# PowerBoard.net
KiCad netlist of a schematic drawn in EAGLE
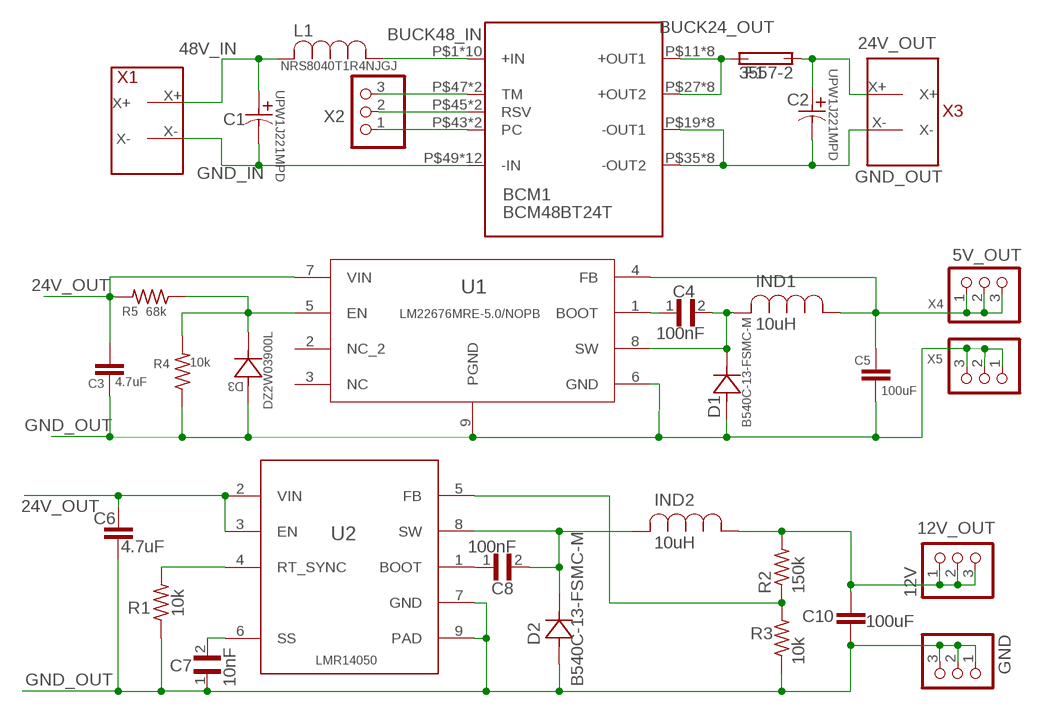
[diagram p0: schematic, sheet 1]

(export (version "E")
  (design (tool "Eeschema 10.0.6"))
  (components
    (comp (ref "12V")
      (value "9-146281-0")
      (footprint "eagle-import:TE_9-146281-0")
      (fields (field (name "MF") "TE Connectivity"))
      (libsource (lib "eagle-import") (part "9-146281-0"))
    )
    (comp (ref "BCM1")
      (value "BCM48BT24T")
      (footprint "eagle-import:BCM48BT24T")
      (libsource (lib "eagle-import") (part "BCM48BT24T"))
    )
    (comp (ref "C1")
      (value "UPW1J221MPD")
      (footprint "eagle-import:PCAP_10X20-THRU-ELECT")
      (libsource (lib "eagle-import") (part "UPW1J221MPD"))
    )
    (comp (ref "C2")
      (value "UPW1J221MPD")
      (footprint "eagle-import:PCAP_10X20-THRU-ELECT")
      (libsource (lib "eagle-import") (part "UPW1J221MPD"))
    )
    (comp (ref "C3")
      (value "4.7uF")
      (footprint "eagle-import:0603")
      (libsource (lib "eagle-import") (part "4.7UF0603"))
    )
    (comp (ref "C4")
      (value "100nF")
      (footprint "eagle-import:CAPC2012X135N")
      (fields (field (name "MF") "Murata Electronics") (field (name "MP") "GRM21BR60E107ME15L"))
      (libsource (lib "eagle-import") (part "GRM21BR60E107ME15L"))
    )
    (comp (ref "C5")
      (value "100uF")
      (footprint "eagle-import:1210")
      (libsource (lib "eagle-import") (part "10UF-1210-50V-20%"))
    )
    (comp (ref "C6")
      (value "4.7uF")
      (footprint "eagle-import:0603")
      (libsource (lib "eagle-import") (part "4.7UF0603"))
    )
    (comp (ref "C7")
      (value "10nF")
      (footprint "eagle-import:CAPC2012X135N")
      (fields (field (name "MF") "Murata Electronics") (field (name "MP") "GRM21BR60E107ME15L"))
      (libsource (lib "eagle-import") (part "GRM21BR60E107ME15L"))
    )
    (comp (ref "C8")
      (value "100nF")
      (footprint "eagle-import:CAPC2012X135N")
      (fields (field (name "MF") "Murata Electronics") (field (name "MP") "GRM21BR60E107ME15L"))
      (libsource (lib "eagle-import") (part "GRM21BR60E107ME15L"))
    )
    (comp (ref "C10")
      (value "100uF")
      (footprint "eagle-import:1210")
      (libsource (lib "eagle-import") (part "10UF-1210-50V-20%"))
    )
    (comp (ref "D1")
      (value "B540C-13-FSMC-M")
      (footprint "eagle-import:SMC-M")
      (fields (field (name "MANUFACTURER_PART_NUMBER") "B540C13F"))
      (libsource (lib "eagle-import") (part "B540C-13-FSMC-M"))
    )
    (comp (ref "D2")
      (value "B540C-13-FSMC-M")
      (footprint "eagle-import:SMC-M")
      (fields (field (name "MANUFACTURER_PART_NUMBER") "B540C13F"))
      (libsource (lib "eagle-import") (part "B540C-13-FSMC-M"))
    )
    (comp (ref "D3")
      (value "DZ2W03900L")
      (footprint "eagle-import:MINI2-F3-B")
      (libsource (lib "eagle-import") (part "DZ2W03900L"))
    )
    (comp (ref "F1")
      (value "3557-2")
      (footprint "eagle-import:FUSE_3557-2")
      (fields (field (name "MF") "Keystone"))
      (libsource (lib "eagle-import") (part "3557-2"))
    )
    (comp (ref "GND")
      (value "9-146281-0")
      (footprint "eagle-import:TE_9-146281-0")
      (fields (field (name "MF") "TE Connectivity"))
      (libsource (lib "eagle-import") (part "9-146281-0"))
    )
    (comp (ref "IND1")
      (value "10uH")
      (footprint "eagle-import:11.15X10")
      (libsource (lib "eagle-import") (part "ASPI-1040HIA"))
    )
    (comp (ref "IND2")
      (value "10uH")
      (footprint "eagle-import:11.15X10")
      (libsource (lib "eagle-import") (part "ASPI-1040HIA"))
    )
    (comp (ref "L1")
      (value "NRS8040T1R4NJGJ")
      (footprint "eagle-import:IND_TAIYO_NRS8040")
      (libsource (lib "eagle-import") (part "NRS8040T1R4NJGJ"))
    )
    (comp (ref "R1")
      (value "10k")
      (footprint "eagle-import:R0603")
      (libsource (lib "eagle-import") (part "R-US_R0603"))
    )
    (comp (ref "R2")
      (value "150k")
      (footprint "eagle-import:R0603")
      (libsource (lib "eagle-import") (part "R-US_R0603"))
    )
    (comp (ref "R3")
      (value "10k")
      (footprint "eagle-import:R0603")
      (libsource (lib "eagle-import") (part "R-US_R0603"))
    )
    (comp (ref "R4")
      (value "10k")
      (footprint "eagle-import:R0603")
      (libsource (lib "eagle-import") (part "R-US_R0603"))
    )
    (comp (ref "R5")
      (value "68k")
      (footprint "eagle-import:R0603")
      (libsource (lib "eagle-import") (part "R-US_R0603"))
    )
    (comp (ref "U1")
      (value "LM22676MRE-5.0/NOPB")
      (footprint "eagle-import:MRA08B")
      (fields (field (name "MANUFACTURER_PART_NUMBER") "LM22676MRE5.0NOPB"))
      (libsource (lib "eagle-import") (part "LM22676MRE-5.0/NOPB"))
    )
    (comp (ref "U2")
      (value "LMR14050")
      (footprint "eagle-import:DDA0008E_N")
      (fields
        (field (name "MANUFACTURER") "Texas Instruments")
        (field (name "MANUFACTURER_PART_NUMBER") "LMR14050SDDAR")
      )
      (libsource (lib "eagle-import") (part "LMR14050SDDAR"))
    )
    (comp (ref "X1")
      (value "XT60")
      (footprint "eagle-import:XT60")
      (libsource (lib "eagle-import") (part "XT60_XT60"))
    )
    (comp (ref "X2")
      (value "9-146281-0")
      (footprint "eagle-import:TE_9-146281-0")
      (fields (field (name "MF") "TE Connectivity"))
      (libsource (lib "eagle-import") (part "9-146281-0"))
    )
    (comp (ref "X3")
      (value "XT60")
      (footprint "eagle-import:XT60")
      (libsource (lib "eagle-import") (part "XT60_XT60"))
    )
    (comp (ref "X4")
      (value "9-146281-0")
      (footprint "eagle-import:TE_9-146281-0")
      (fields (field (name "MF") "TE Connectivity"))
      (libsource (lib "eagle-import") (part "9-146281-0"))
    )
    (comp (ref "X5")
      (value "9-146281-0")
      (footprint "eagle-import:TE_9-146281-0")
      (fields (field (name "MF") "TE Connectivity"))
      (libsource (lib "eagle-import") (part "9-146281-0"))
    )
  )
  (nets
    (net (code "1") (name "/5V_OUT") (class "Default")
      (node (ref "C5") (pin "1") (pinfunction "1_1") (pintype "passive"))
      (node (ref "IND1") (pin "1") (pinfunction "1_1") (pintype "passive"))
      (node (ref "U1") (pin "4") (pinfunction "FB_4") (pintype "input"))
      (node (ref "X4") (pin "1") (pinfunction "1_1") (pintype "passive"))
      (node (ref "X4") (pin "2") (pinfunction "2_2") (pintype "passive"))
      (node (ref "X4") (pin "3") (pinfunction "3_3") (pintype "passive"))
    )
    (net (code "2") (name "/12V_OUT") (class "Default")
      (node (ref "12V") (pin "1") (pinfunction "1_1") (pintype "passive"))
      (node (ref "12V") (pin "2") (pinfunction "2_2") (pintype "passive"))
      (node (ref "12V") (pin "3") (pinfunction "3_3") (pintype "passive"))
      (node (ref "C10") (pin "1") (pinfunction "1_1") (pintype "passive"))
      (node (ref "IND2") (pin "1") (pinfunction "1_1") (pintype "passive"))
      (node (ref "R2") (pin "2") (pinfunction "2_2") (pintype "passive"))
    )
    (net (code "3") (name "/24V_OUT") (class "Default")
      (node (ref "C2") (pin "1") (pinfunction "11_1") (pintype "passive"))
      (node (ref "C3") (pin "1") (pinfunction "1_1") (pintype "passive"))
      (node (ref "C6") (pin "1") (pinfunction "1_1") (pintype "passive"))
      (node (ref "F1") (pin "3") (pinfunction "2A_3") (pintype "passive"))
      (node (ref "F1") (pin "4") (pinfunction "2A_4") (pintype "passive"))
      (node (ref "R5") (pin "2") (pinfunction "2_2") (pintype "passive"))
      (node (ref "U1") (pin "7") (pinfunction "VIN_7") (pintype "power_in"))
      (node (ref "U2") (pin "2") (pinfunction "VIN_2") (pintype "power_in"))
      (node (ref "U2") (pin "3") (pinfunction "EN_3") (pintype "input"))
      (node (ref "X3") (pin "X+") (pinfunction "X+_X+") (pintype "bidirectional"))
    )
    (net (code "4") (name "/48V_IN") (class "Default")
      (node (ref "C1") (pin "1") (pinfunction "11_1") (pintype "passive"))
      (node (ref "L1") (pin "2") (pinfunction "2_2") (pintype "passive"))
      (node (ref "X1") (pin "X+") (pinfunction "X+_X+") (pintype "bidirectional"))
    )
    (net (code "5") (name "/BUCK24_OUT") (class "Default")
      (node (ref "BCM1") (pin "P$11") (pinfunction "+OUT1_P$11") (pintype "output"))
      (node (ref "BCM1") (pin "P$12") (pinfunction "+OUT1_P$12") (pintype "output"))
      (node (ref "BCM1") (pin "P$13") (pinfunction "+OUT1_P$13") (pintype "output"))
      (node (ref "BCM1") (pin "P$14") (pinfunction "+OUT1_P$14") (pintype "output"))
      (node (ref "BCM1") (pin "P$15") (pinfunction "+OUT1_P$15") (pintype "output"))
      (node (ref "BCM1") (pin "P$16") (pinfunction "+OUT1_P$16") (pintype "output"))
      (node (ref "BCM1") (pin "P$17") (pinfunction "+OUT1_P$17") (pintype "output"))
      (node (ref "BCM1") (pin "P$18") (pinfunction "+OUT1_P$18") (pintype "output"))
      (node (ref "BCM1") (pin "P$27") (pinfunction "+OUT2_P$27") (pintype "output"))
      (node (ref "BCM1") (pin "P$28") (pinfunction "+OUT2_P$28") (pintype "output"))
      (node (ref "BCM1") (pin "P$29") (pinfunction "+OUT2_P$29") (pintype "output"))
      (node (ref "BCM1") (pin "P$30") (pinfunction "+OUT2_P$30") (pintype "output"))
      (node (ref "BCM1") (pin "P$31") (pinfunction "+OUT2_P$31") (pintype "output"))
      (node (ref "BCM1") (pin "P$32") (pinfunction "+OUT2_P$32") (pintype "output"))
      (node (ref "BCM1") (pin "P$33") (pinfunction "+OUT2_P$33") (pintype "output"))
      (node (ref "BCM1") (pin "P$34") (pinfunction "+OUT2_P$34") (pintype "output"))
      (node (ref "F1") (pin "1") (pinfunction "1A_1") (pintype "passive"))
      (node (ref "F1") (pin "2") (pinfunction "1A_2") (pintype "passive"))
    )
    (net (code "6") (name "/BUCK48_IN") (class "Default")
      (node (ref "BCM1") (pin "P$1") (pinfunction "+IN_P$1") (pintype "input"))
      (node (ref "BCM1") (pin "P$10") (pinfunction "+IN_P$10") (pintype "input"))
      (node (ref "BCM1") (pin "P$2") (pinfunction "+IN_P$2") (pintype "input"))
      (node (ref "BCM1") (pin "P$3") (pinfunction "+IN_P$3") (pintype "input"))
      (node (ref "BCM1") (pin "P$4") (pinfunction "+IN_P$4") (pintype "input"))
      (node (ref "BCM1") (pin "P$5") (pinfunction "+IN_P$5") (pintype "input"))
      (node (ref "BCM1") (pin "P$6") (pinfunction "+IN_P$6") (pintype "input"))
      (node (ref "BCM1") (pin "P$7") (pinfunction "+IN_P$7") (pintype "input"))
      (node (ref "BCM1") (pin "P$8") (pinfunction "+IN_P$8") (pintype "input"))
      (node (ref "BCM1") (pin "P$9") (pinfunction "+IN_P$9") (pintype "input"))
      (node (ref "L1") (pin "1") (pinfunction "1_1") (pintype "passive"))
    )
    (net (code "7") (name "/GND_IN") (class "Default")
      (node (ref "BCM1") (pin "P$49") (pinfunction "-IN_P$49") (pintype "input"))
      (node (ref "BCM1") (pin "P$50") (pinfunction "-IN_P$50") (pintype "input"))
      (node (ref "BCM1") (pin "P$51") (pinfunction "-IN_P$51") (pintype "input"))
      (node (ref "BCM1") (pin "P$52") (pinfunction "-IN_P$52") (pintype "input"))
      (node (ref "BCM1") (pin "P$53") (pinfunction "-IN_P$53") (pintype "input"))
      (node (ref "BCM1") (pin "P$54") (pinfunction "-IN_P$54") (pintype "input"))
      (node (ref "BCM1") (pin "P$55") (pinfunction "-IN_P$55") (pintype "input"))
      (node (ref "BCM1") (pin "P$56") (pinfunction "-IN_P$56") (pintype "input"))
      (node (ref "BCM1") (pin "P$57") (pinfunction "-IN_P$57") (pintype "input"))
      (node (ref "BCM1") (pin "P$58") (pinfunction "-IN_P$58") (pintype "input"))
      (node (ref "BCM1") (pin "P$59") (pinfunction "-IN_P$59") (pintype "input"))
      (node (ref "BCM1") (pin "P$60") (pinfunction "-IN_P$60") (pintype "input"))
      (node (ref "C1") (pin "2") (pinfunction "22_2") (pintype "passive"))
      (node (ref "X1") (pin "X-") (pinfunction "X-_X-") (pintype "bidirectional"))
    )
    (net (code "8") (name "/GND_OUT") (class "Default")
      (node (ref "BCM1") (pin "P$19") (pinfunction "-OUT1_P$19") (pintype "output"))
      (node (ref "BCM1") (pin "P$20") (pinfunction "-OUT1_P$20") (pintype "output"))
      (node (ref "BCM1") (pin "P$21") (pinfunction "-OUT1_P$21") (pintype "output"))
      (node (ref "BCM1") (pin "P$22") (pinfunction "-OUT1_P$22") (pintype "output"))
      (node (ref "BCM1") (pin "P$23") (pinfunction "-OUT1_P$23") (pintype "output"))
      (node (ref "BCM1") (pin "P$24") (pinfunction "-OUT1_P$24") (pintype "output"))
      (node (ref "BCM1") (pin "P$25") (pinfunction "-OUT1_P$25") (pintype "output"))
      (node (ref "BCM1") (pin "P$26") (pinfunction "-OUT1_P$26") (pintype "output"))
      (node (ref "BCM1") (pin "P$35") (pinfunction "-OUT2_P$35") (pintype "output"))
      (node (ref "BCM1") (pin "P$36") (pinfunction "-OUT2_P$36") (pintype "output"))
      (node (ref "BCM1") (pin "P$37") (pinfunction "-OUT2_P$37") (pintype "output"))
      (node (ref "BCM1") (pin "P$38") (pinfunction "-OUT2_P$38") (pintype "output"))
      (node (ref "BCM1") (pin "P$39") (pinfunction "-OUT2_P$39") (pintype "output"))
      (node (ref "BCM1") (pin "P$40") (pinfunction "-OUT2_P$40") (pintype "output"))
      (node (ref "BCM1") (pin "P$41") (pinfunction "-OUT2_P$41") (pintype "output"))
      (node (ref "BCM1") (pin "P$42") (pinfunction "-OUT2_P$42") (pintype "output"))
      (node (ref "C10") (pin "2") (pinfunction "2_2") (pintype "passive"))
      (node (ref "C2") (pin "2") (pinfunction "22_2") (pintype "passive"))
      (node (ref "C3") (pin "2") (pinfunction "2_2") (pintype "passive"))
      (node (ref "C5") (pin "2") (pinfunction "2_2") (pintype "passive"))
      (node (ref "C6") (pin "2") (pinfunction "2_2") (pintype "passive"))
      (node (ref "C7") (pin "1") (pinfunction "1_1") (pintype "passive"))
      (node (ref "D1") (pin "2") (pinfunction "21_2") (pintype "passive"))
      (node (ref "D2") (pin "2") (pinfunction "21_2") (pintype "passive"))
      (node (ref "D3") (pin "2") (pinfunction "22_2") (pintype "passive"))
      (node (ref "GND") (pin "1") (pinfunction "1_1") (pintype "passive"))
      (node (ref "GND") (pin "2") (pinfunction "2_2") (pintype "passive"))
      (node (ref "GND") (pin "3") (pinfunction "3_3") (pintype "passive"))
      (node (ref "R1") (pin "1") (pinfunction "1_1") (pintype "passive"))
      (node (ref "R3") (pin "1") (pinfunction "1_1") (pintype "passive"))
      (node (ref "R4") (pin "1") (pinfunction "1_1") (pintype "passive"))
      (node (ref "U1") (pin "6") (pinfunction "GND_6") (pintype "power_in"))
      (node (ref "U1") (pin "9") (pinfunction "PGND_9") (pintype "power_in"))
      (node (ref "U2") (pin "7") (pinfunction "GND_7") (pintype "power_in"))
      (node (ref "U2") (pin "9") (pinfunction "PAD_9") (pintype "power_in"))
      (node (ref "X3") (pin "X-") (pinfunction "X-_X-") (pintype "bidirectional"))
      (node (ref "X5") (pin "1") (pinfunction "1_1") (pintype "passive"))
      (node (ref "X5") (pin "2") (pinfunction "2_2") (pintype "passive"))
      (node (ref "X5") (pin "3") (pinfunction "3_3") (pintype "passive"))
    )
    (net (code "9") (name "Net-(BCM1-PC-PadP$43)") (class "Default")
      (node (ref "BCM1") (pin "P$43") (pinfunction "PC_P$43") (pintype "bidirectional"))
      (node (ref "BCM1") (pin "P$44") (pinfunction "PC_P$44") (pintype "bidirectional"))
      (node (ref "X2") (pin "1") (pinfunction "1_1") (pintype "passive"))
    )
    (net (code "10") (name "Net-(BCM1-RSV-PadP$45)") (class "Default")
      (node (ref "BCM1") (pin "P$45") (pinfunction "RSV_P$45") (pintype "bidirectional"))
      (node (ref "BCM1") (pin "P$46") (pinfunction "RSV_P$46") (pintype "bidirectional"))
      (node (ref "X2") (pin "2") (pinfunction "2_2") (pintype "passive"))
    )
    (net (code "11") (name "Net-(BCM1-TM-PadP$47)") (class "Default")
      (node (ref "BCM1") (pin "P$47") (pinfunction "TM_P$47") (pintype "bidirectional"))
      (node (ref "BCM1") (pin "P$48") (pinfunction "TM_P$48") (pintype "bidirectional"))
      (node (ref "X2") (pin "3") (pinfunction "3_3") (pintype "passive"))
    )
    (net (code "12") (name "Net-(D1-12)") (class "Default")
      (node (ref "C4") (pin "2") (pinfunction "2_2") (pintype "passive"))
      (node (ref "D1") (pin "1") (pinfunction "12_1") (pintype "passive"))
      (node (ref "IND1") (pin "2") (pinfunction "2_2") (pintype "passive"))
      (node (ref "U1") (pin "8") (pinfunction "SW_8") (pintype "power_in"))
    )
    (net (code "13") (name "Net-(D2-12)") (class "Default")
      (node (ref "C8") (pin "2") (pinfunction "2_2") (pintype "passive"))
      (node (ref "D2") (pin "1") (pinfunction "12_1") (pintype "passive"))
      (node (ref "IND2") (pin "2") (pinfunction "2_2") (pintype "passive"))
      (node (ref "U2") (pin "8") (pinfunction "SW_8") (pintype "power_in"))
    )
    (net (code "14") (name "Net-(D3-11)") (class "Default")
      (node (ref "D3") (pin "1") (pinfunction "11_1") (pintype "passive"))
      (node (ref "R4") (pin "2") (pinfunction "2_2") (pintype "passive"))
      (node (ref "R5") (pin "1") (pinfunction "1_1") (pintype "passive"))
      (node (ref "U1") (pin "5") (pinfunction "EN_5") (pintype "input"))
    )
    (net (code "15") (name "Net-(U1-BOOT)") (class "Default")
      (node (ref "C4") (pin "1") (pinfunction "1_1") (pintype "passive"))
      (node (ref "U1") (pin "1") (pinfunction "BOOT_1") (pintype "passive"))
    )
    (net (code "16") (name "Net-(U2-BOOT)") (class "Default")
      (node (ref "C8") (pin "1") (pinfunction "1_1") (pintype "passive"))
      (node (ref "U2") (pin "1") (pinfunction "BOOT_1") (pintype "passive"))
    )
    (net (code "17") (name "Net-(U2-FB)") (class "Default")
      (node (ref "R2") (pin "1") (pinfunction "1_1") (pintype "passive"))
      (node (ref "R3") (pin "2") (pinfunction "2_2") (pintype "passive"))
      (node (ref "U2") (pin "5") (pinfunction "FB_5") (pintype "input"))
    )
    (net (code "18") (name "Net-(U2-RT_SYNC)") (class "Default")
      (node (ref "R1") (pin "2") (pinfunction "2_2") (pintype "passive"))
      (node (ref "U2") (pin "4") (pinfunction "RT_SYNC_4") (pintype "passive"))
    )
    (net (code "19") (name "Net-(U2-SS)") (class "Default")
      (node (ref "C7") (pin "2") (pinfunction "2_2") (pintype "passive"))
      (node (ref "U2") (pin "6") (pinfunction "SS_6") (pintype "input"))
    )
    (net (code "20") (name "unconnected-(U1-NC-Pad3)") (class "Default")
      (node (ref "U1") (pin "3") (pinfunction "NC_3") (pintype "passive"))
    )
    (net (code "21") (name "unconnected-(U1-NC_2-Pad2)") (class "Default")
      (node (ref "U1") (pin "2") (pinfunction "NC_2_2") (pintype "passive"))
    )
  )
)
